# Develop_board.net
KiCad netlist of a schematic drawn in Altium Designer
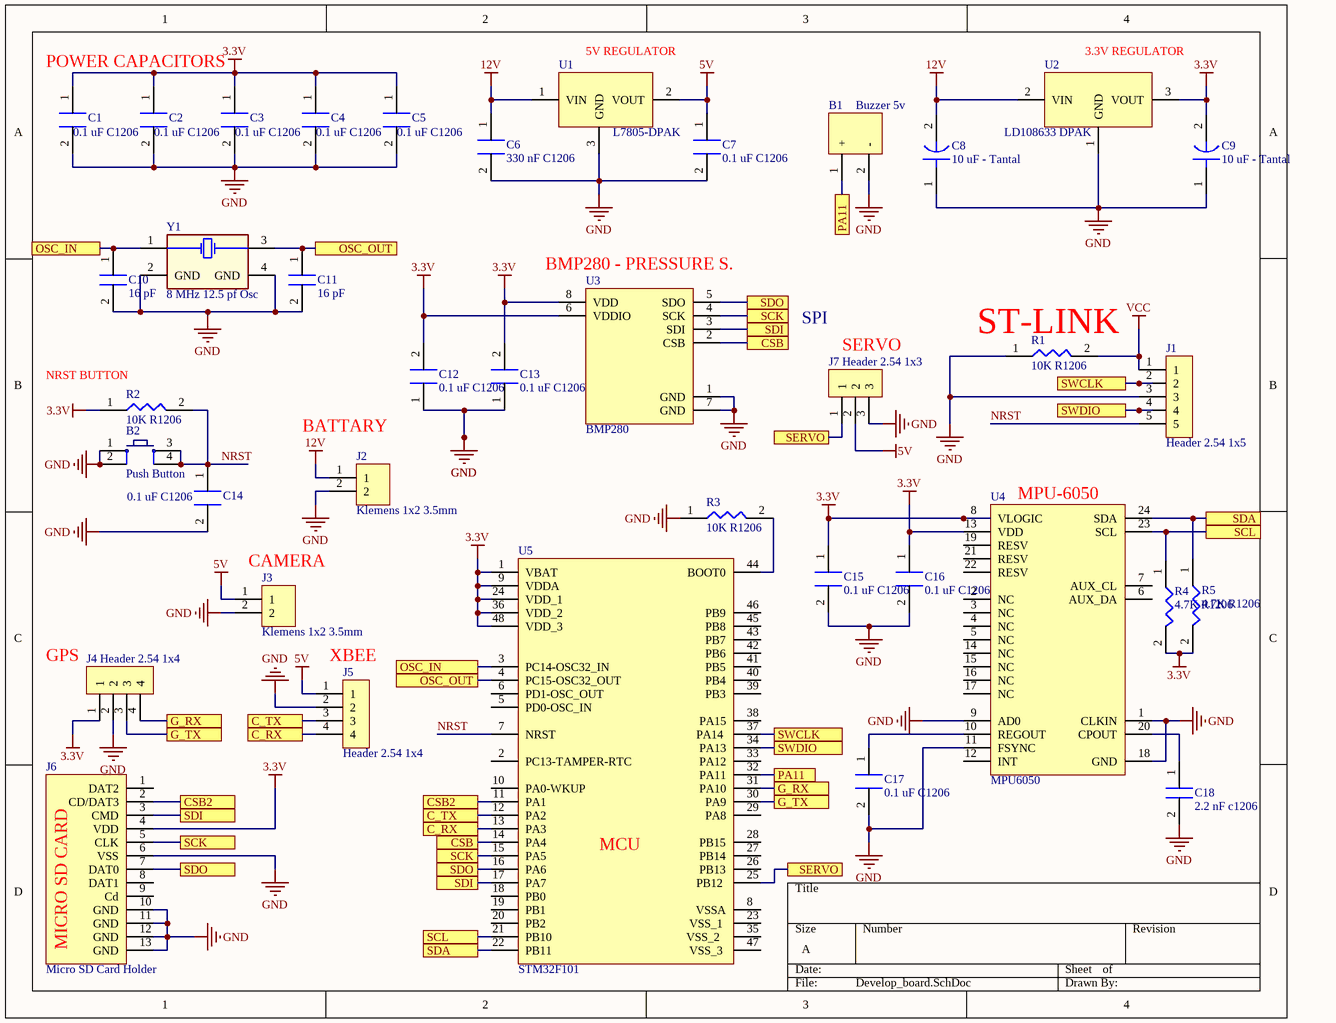
[diagram p0: Develop_board.SchDoc]

(export (version "E")
  (design (tool "Eeschema 10.0.6"))
  (components
    (comp (ref "B1")
      (value "Buzzer 5v")
      (footprint "Buzzer 5v")
      (libsource (lib "Schlib1") (part "Buzzer 5v"))
    )
    (comp (ref "B2")
      (value "Push Button")
      (footprint "PUSB BUTTON-SMD")
      (description "Smd Push Button")
      (libsource (lib "Schlib1") (part "Push Button"))
    )
    (comp (ref "C1")
      (value "0.1 uF C1206")
      (footprint "C1206")
      (libsource (lib "Schlib1") (part "0.1 uF C1206"))
    )
    (comp (ref "C2")
      (value "0.1 uF C1206")
      (footprint "C1206")
      (libsource (lib "Schlib1") (part "0.1 uF C1206"))
    )
    (comp (ref "C3")
      (value "0.1 uF C1206")
      (footprint "C1206")
      (libsource (lib "Schlib1") (part "0.1 uF C1206"))
    )
    (comp (ref "C4")
      (value "0.1 uF C1206")
      (footprint "C1206")
      (libsource (lib "Schlib1") (part "0.1 uF C1206"))
    )
    (comp (ref "C5")
      (value "0.1 uF C1206")
      (footprint "C1206")
      (libsource (lib "Schlib1") (part "0.1 uF C1206"))
    )
    (comp (ref "C6")
      (value "330 nF C1206")
      (footprint "C1206")
      (libsource (lib "Schlib1") (part "330 nF C1206"))
    )
    (comp (ref "C7")
      (value "0.1 uF C1206")
      (footprint "C1206")
      (libsource (lib "Schlib1") (part "0.1 uF C1206"))
    )
    (comp (ref "C8")
      (value "10 uF - Tantal")
      (footprint "C1206- TANTAL")
      (libsource (lib "Schlib1") (part "10 uF - Tantal"))
    )
    (comp (ref "C9")
      (value "10 uF - Tantal")
      (footprint "C1206- TANTAL")
      (libsource (lib "Schlib1") (part "10 uF - Tantal"))
    )
    (comp (ref "C10") (value "16 pF") (footprint "C1206") (libsource (lib "Schlib1") (part "16 pF")))
    (comp (ref "C11") (value "16 pF") (footprint "C1206") (libsource (lib "Schlib1") (part "16 pF")))
    (comp (ref "C12")
      (value "0.1 uF C1206")
      (footprint "C1206")
      (libsource (lib "Schlib1") (part "0.1 uF C1206"))
    )
    (comp (ref "C13")
      (value "0.1 uF C1206")
      (footprint "C1206")
      (libsource (lib "Schlib1") (part "0.1 uF C1206"))
    )
    (comp (ref "C14")
      (value "0.1 uF C1206")
      (footprint "C1206")
      (libsource (lib "Schlib1") (part "0.1 uF C1206"))
    )
    (comp (ref "C15")
      (value "0.1 uF C1206")
      (footprint "C1206")
      (libsource (lib "Schlib1") (part "0.1 uF C1206"))
    )
    (comp (ref "C16")
      (value "0.1 uF C1206")
      (footprint "C1206")
      (libsource (lib "Schlib1") (part "0.1 uF C1206"))
    )
    (comp (ref "C17")
      (value "0.1 uF C1206")
      (footprint "C1206")
      (libsource (lib "Schlib1") (part "0.1 uF C1206"))
    )
    (comp (ref "C18")
      (value "2.2 nF c1206")
      (footprint "C1206")
      (libsource (lib "Schlib1") (part "2.2 nF c1206"))
    )
    (comp (ref "J1")
      (value "Header 2.54 1x5")
      (footprint "Header 2.54 1x5")
      (libsource (lib "Schlib1") (part "Header 2.54 1x5"))
    )
    (comp (ref "J2")
      (value "Klemens 1x2 3.5mm")
      (footprint "Klemens 1x2 - 3.5mm")
      (libsource (lib "Schlib1") (part "Klemens 1x2 3.5mm"))
    )
    (comp (ref "J3")
      (value "Klemens 1x2 3.5mm")
      (footprint "Klemens 1x2 - 3.5mm")
      (libsource (lib "Schlib1") (part "Klemens 1x2 3.5mm"))
    )
    (comp (ref "J4")
      (value "Header 2.54 1x4")
      (footprint "Header 2.54 1x4")
      (libsource (lib "Schlib1") (part "Header 2.54 1x4"))
    )
    (comp (ref "J5")
      (value "Header 2.54 1x4")
      (footprint "Header 2.54 1x4")
      (libsource (lib "") (part "Header 2.54 1x4_1"))
    )
    (comp (ref "J6")
      (value "Micro SD Card Holder")
      (footprint "Micro SD Card Holder")
      (libsource (lib "Schlib1") (part "Micro SD Card Holder"))
    )
    (comp (ref "J7")
      (value "Header 2.54 1x3")
      (footprint "Header 2.54 1x3")
      (libsource (lib "Schlib1") (part "Header 2.54 1x3"))
    )
    (comp (ref "R1")
      (value "10K R1206")
      (footprint "R1206 Resistor")
      (description "4.7K R1206")
      (libsource (lib "Schlib1") (part "4.7K R1206"))
    )
    (comp (ref "R2")
      (value "10K R1206")
      (footprint "R1206 Resistor")
      (libsource (lib "Schlib1") (part "10K R1206"))
    )
    (comp (ref "R3")
      (value "10K R1206")
      (footprint "R1206 Resistor")
      (libsource (lib "Schlib1") (part "10K R1206"))
    )
    (comp (ref "R4")
      (value "4.7K R1206")
      (footprint "R1206 Resistor")
      (libsource (lib "Schlib1") (part "4.7K R1206"))
    )
    (comp (ref "R5")
      (value "4.7K R1206")
      (footprint "R1206 Resistor")
      (libsource (lib "Schlib1") (part "4.7K R1206"))
    )
    (comp (ref "U1")
      (value "L7805-DPAK")
      (footprint "DPAK228P972X230-3N")
      (description "L7805 5V REGULATOR. SMD PAKET")
      (libsource (lib "Schlib1") (part "L7805-DPAK"))
    )
    (comp (ref "U2")
      (value "LD108633 DPAK")
      (footprint "DPAK228P972X230-3N")
      (description "LD1086 3.3V REGULATOR")
      (libsource (lib "Schlib1") (part "LD108633 DPAK"))
    )
    (comp (ref "U3")
      (value "BMP280")
      (footprint "BMP280")
      (description "BMP280 SENSOR")
      (libsource (lib "Schlib1") (part "BMP280"))
    )
    (comp (ref "U4")
      (value "MPU6050")
      (footprint "QFN50P400X400X90_HS-25N")
      (description "MPU6050 GYRO SENSOR")
      (libsource (lib "Schlib1") (part "MPU6050"))
    )
    (comp (ref "U5")
      (value "STM32F101")
      (footprint "LQFP48-STM")
      (description "STM32F101 48 PİNLİ MİKROİŞLEMCİ")
      (libsource (lib "Schlib1") (part "STM32F101"))
    )
    (comp (ref "Y1")
      (value "8 MHz 12.5 pf Osc")
      (footprint "8 MHZ Osc.")
      (libsource (lib "Schlib1") (part "8 MHz 12.5 pf Osc"))
    )
  )
  (nets
    (net (code "1") (name "/CSB") (class "Default")
      (node (ref "U3") (pin "2") (pinfunction "CSB_2") (pintype "passive"))
      (node (ref "U5") (pin "14") (pinfunction "PA4_14") (pintype "passive"))
    )
    (net (code "2") (name "/CSB2") (class "Default")
      (node (ref "J6") (pin "2") (pinfunction "CD/DAT3_2") (pintype "passive"))
      (node (ref "U5") (pin "11") (pinfunction "PA1_11") (pintype "passive"))
    )
    (net (code "3") (name "/C_RX") (class "Default")
      (node (ref "J5") (pin "4") (pinfunction "4_4") (pintype "passive"))
      (node (ref "U5") (pin "13") (pinfunction "PA3_13") (pintype "passive"))
    )
    (net (code "4") (name "/C_TX") (class "Default")
      (node (ref "J5") (pin "3") (pinfunction "3_3") (pintype "passive"))
      (node (ref "U5") (pin "12") (pinfunction "PA2_12") (pintype "passive"))
    )
    (net (code "5") (name "/G_RX") (class "Default")
      (node (ref "J4") (pin "4") (pinfunction "4_4") (pintype "passive"))
      (node (ref "U5") (pin "31") (pinfunction "PA10_31") (pintype "passive"))
    )
    (net (code "6") (name "/G_TX") (class "Default")
      (node (ref "J4") (pin "3") (pinfunction "3_3") (pintype "passive"))
      (node (ref "U5") (pin "30") (pinfunction "PA9_30") (pintype "passive"))
    )
    (net (code "7") (name "/NRST") (class "Default")
      (node (ref "B2") (pin "3") (pinfunction "3_3") (pintype "passive"))
      (node (ref "B2") (pin "4") (pinfunction "4_4") (pintype "passive"))
      (node (ref "C14") (pin "1") (pinfunction "1_1") (pintype "passive"))
      (node (ref "J1") (pin "5") (pinfunction "5_5") (pintype "passive"))
      (node (ref "R2") (pin "2") (pinfunction "2_2") (pintype "passive"))
      (node (ref "U5") (pin "7") (pinfunction "NRST_7") (pintype "passive"))
    )
    (net (code "8") (name "/OSC_IN") (class "Default")
      (node (ref "C10") (pin "1") (pinfunction "1_1") (pintype "passive"))
      (node (ref "U5") (pin "3") (pinfunction "PC14-OSC32_IN_3") (pintype "passive"))
      (node (ref "Y1") (pin "1") (pintype "power_in"))
    )
    (net (code "9") (name "/OSC_OUT") (class "Default")
      (node (ref "C11") (pin "1") (pinfunction "1_1") (pintype "passive"))
      (node (ref "U5") (pin "4") (pinfunction "PC15-OSC32_OUT_4") (pintype "passive"))
      (node (ref "Y1") (pin "3") (pintype "passive"))
    )
    (net (code "10") (name "/PA11") (class "Default")
      (node (ref "B1") (pin "1") (pinfunction "+_1") (pintype "passive"))
      (node (ref "U5") (pin "32") (pinfunction "PA11_32") (pintype "passive"))
    )
    (net (code "11") (name "/SCK") (class "Default")
      (node (ref "J6") (pin "5") (pinfunction "CLK_5") (pintype "passive"))
      (node (ref "U3") (pin "4") (pinfunction "SCK_4") (pintype "passive"))
      (node (ref "U5") (pin "15") (pinfunction "PA5_15") (pintype "passive"))
    )
    (net (code "12") (name "/SCL") (class "Default")
      (node (ref "R4") (pin "1") (pinfunction "1_1") (pintype "passive"))
      (node (ref "U4") (pin "23") (pinfunction "SCL_23") (pintype "passive"))
      (node (ref "U5") (pin "21") (pinfunction "PB10_21") (pintype "passive"))
    )
    (net (code "13") (name "/SDA") (class "Default")
      (node (ref "R5") (pin "1") (pinfunction "1_1") (pintype "passive"))
      (node (ref "U4") (pin "24") (pinfunction "SDA_24") (pintype "passive"))
      (node (ref "U5") (pin "22") (pinfunction "PB11_22") (pintype "passive"))
    )
    (net (code "14") (name "/SDI") (class "Default")
      (node (ref "J6") (pin "3") (pinfunction "CMD_3") (pintype "passive"))
      (node (ref "U3") (pin "3") (pinfunction "SDI_3") (pintype "passive"))
      (node (ref "U5") (pin "17") (pinfunction "PA7_17") (pintype "passive"))
    )
    (net (code "15") (name "/SDO") (class "Default")
      (node (ref "J6") (pin "7") (pinfunction "DAT0_7") (pintype "passive"))
      (node (ref "U3") (pin "5") (pinfunction "SDO_5") (pintype "passive"))
      (node (ref "U5") (pin "16") (pinfunction "PA6_16") (pintype "passive"))
    )
    (net (code "16") (name "/SERVO") (class "Default")
      (node (ref "J7") (pin "1") (pinfunction "1_1") (pintype "passive"))
      (node (ref "U5") (pin "25") (pinfunction "PB12_25") (pintype "passive"))
    )
    (net (code "17") (name "/SWCLK") (class "Default")
      (node (ref "J1") (pin "2") (pinfunction "2_2") (pintype "passive"))
      (node (ref "U5") (pin "37") (pinfunction "PA14_37") (pintype "passive"))
    )
    (net (code "18") (name "/SWDIO") (class "Default")
      (node (ref "J1") (pin "4") (pinfunction "4_4") (pintype "passive"))
      (node (ref "U5") (pin "34") (pinfunction "PA13_34") (pintype "passive"))
    )
    (net (code "19") (name "3.3V") (class "Default")
      (node (ref "C1") (pin "1") (pinfunction "1_1") (pintype "passive"))
      (node (ref "C12") (pin "2") (pinfunction "2_2") (pintype "passive"))
      (node (ref "C13") (pin "2") (pinfunction "2_2") (pintype "passive"))
      (node (ref "C15") (pin "1") (pinfunction "1_1") (pintype "passive"))
      (node (ref "C16") (pin "1") (pinfunction "1_1") (pintype "passive"))
      (node (ref "C2") (pin "1") (pinfunction "1_1") (pintype "passive"))
      (node (ref "C3") (pin "1") (pinfunction "1_1") (pintype "passive"))
      (node (ref "C4") (pin "1") (pinfunction "1_1") (pintype "passive"))
      (node (ref "C5") (pin "1") (pinfunction "1_1") (pintype "passive"))
      (node (ref "C9") (pin "2") (pinfunction "2_2") (pintype "passive"))
      (node (ref "J4") (pin "1") (pinfunction "1_1") (pintype "passive"))
      (node (ref "J6") (pin "4") (pinfunction "VDD_4") (pintype "passive"))
      (node (ref "R2") (pin "1") (pinfunction "1_1") (pintype "passive"))
      (node (ref "R4") (pin "2") (pinfunction "2_2") (pintype "passive"))
      (node (ref "R5") (pin "2") (pinfunction "2_2") (pintype "passive"))
      (node (ref "U2") (pin "3") (pinfunction "VOUT_3") (pintype "passive"))
      (node (ref "U3") (pin "6") (pinfunction "VDDIO_6") (pintype "passive"))
      (node (ref "U3") (pin "8") (pinfunction "VDD_8") (pintype "passive"))
      (node (ref "U4") (pin "13") (pinfunction "VDD_13") (pintype "passive"))
      (node (ref "U4") (pin "8") (pinfunction "VLOGIC_8") (pintype "passive"))
      (node (ref "U5") (pin "1") (pinfunction "VBAT_1") (pintype "passive"))
      (node (ref "U5") (pin "24") (pinfunction "VDD_1_24") (pintype "passive"))
      (node (ref "U5") (pin "36") (pinfunction "VDD_2_36") (pintype "passive"))
      (node (ref "U5") (pin "48") (pinfunction "VDD_3_48") (pintype "passive"))
      (node (ref "U5") (pin "9") (pinfunction "VDDA_9") (pintype "passive"))
    )
    (net (code "20") (name "5V") (class "Default")
      (node (ref "C7") (pin "1") (pinfunction "1_1") (pintype "passive"))
      (node (ref "J3") (pin "1") (pinfunction "1_1") (pintype "passive"))
      (node (ref "J5") (pin "1") (pinfunction "1_1") (pintype "passive"))
      (node (ref "J7") (pin "2") (pinfunction "2_2") (pintype "passive"))
      (node (ref "U1") (pin "2") (pinfunction "VOUT_2") (pintype "passive"))
    )
    (net (code "21") (name "12V") (class "Default")
      (node (ref "C6") (pin "1") (pinfunction "1_1") (pintype "passive"))
      (node (ref "C8") (pin "2") (pinfunction "2_2") (pintype "passive"))
      (node (ref "J2") (pin "1") (pinfunction "1_1") (pintype "passive"))
      (node (ref "U1") (pin "1") (pinfunction "VIN_1") (pintype "passive"))
      (node (ref "U2") (pin "2") (pinfunction "VIN_2") (pintype "passive"))
    )
    (net (code "22") (name "GND") (class "Default")
      (node (ref "B1") (pin "2") (pinfunction "-_2") (pintype "passive"))
      (node (ref "B2") (pin "1") (pinfunction "1_1") (pintype "passive"))
      (node (ref "B2") (pin "2") (pinfunction "2_2") (pintype "passive"))
      (node (ref "C1") (pin "2") (pinfunction "2_2") (pintype "passive"))
      (node (ref "C10") (pin "2") (pinfunction "2_2") (pintype "passive"))
      (node (ref "C11") (pin "2") (pinfunction "2_2") (pintype "passive"))
      (node (ref "C12") (pin "1") (pinfunction "1_1") (pintype "passive"))
      (node (ref "C13") (pin "1") (pinfunction "1_1") (pintype "passive"))
      (node (ref "C14") (pin "2") (pinfunction "2_2") (pintype "passive"))
      (node (ref "C15") (pin "2") (pinfunction "2_2") (pintype "passive"))
      (node (ref "C16") (pin "2") (pinfunction "2_2") (pintype "passive"))
      (node (ref "C17") (pin "2") (pinfunction "2_2") (pintype "passive"))
      (node (ref "C18") (pin "2") (pinfunction "2_2") (pintype "passive"))
      (node (ref "C2") (pin "2") (pinfunction "2_2") (pintype "passive"))
      (node (ref "C3") (pin "2") (pinfunction "2_2") (pintype "passive"))
      (node (ref "C4") (pin "2") (pinfunction "2_2") (pintype "passive"))
      (node (ref "C5") (pin "2") (pinfunction "2_2") (pintype "passive"))
      (node (ref "C6") (pin "2") (pinfunction "2_2") (pintype "passive"))
      (node (ref "C7") (pin "2") (pinfunction "2_2") (pintype "passive"))
      (node (ref "C8") (pin "1") (pinfunction "1_1") (pintype "passive"))
      (node (ref "C9") (pin "1") (pinfunction "1_1") (pintype "passive"))
      (node (ref "J1") (pin "3") (pinfunction "3_3") (pintype "passive"))
      (node (ref "J2") (pin "2") (pinfunction "2_2") (pintype "passive"))
      (node (ref "J3") (pin "2") (pinfunction "2_2") (pintype "passive"))
      (node (ref "J4") (pin "2") (pinfunction "2_2") (pintype "passive"))
      (node (ref "J5") (pin "2") (pinfunction "2_2") (pintype "passive"))
      (node (ref "J6") (pin "10") (pinfunction "GND_10") (pintype "passive"))
      (node (ref "J6") (pin "11") (pinfunction "GND_11") (pintype "passive"))
      (node (ref "J6") (pin "12") (pinfunction "GND_12") (pintype "passive"))
      (node (ref "J6") (pin "13") (pinfunction "GND_13") (pintype "passive"))
      (node (ref "J6") (pin "6") (pinfunction "VSS_6") (pintype "passive"))
      (node (ref "J7") (pin "3") (pinfunction "3_3") (pintype "passive"))
      (node (ref "R1") (pin "1") (pinfunction "1_1") (pintype "passive"))
      (node (ref "R3") (pin "1") (pinfunction "1_1") (pintype "passive"))
      (node (ref "U1") (pin "3") (pinfunction "GND_3") (pintype "passive"))
      (node (ref "U2") (pin "1") (pinfunction "GND_1") (pintype "passive"))
      (node (ref "U3") (pin "1") (pinfunction "GND_1") (pintype "passive"))
      (node (ref "U3") (pin "7") (pinfunction "GND_7") (pintype "passive"))
      (node (ref "U4") (pin "1") (pinfunction "CLKIN_1") (pintype "passive"))
      (node (ref "U4") (pin "11") (pinfunction "FSYNC_11") (pintype "passive"))
      (node (ref "U4") (pin "18") (pinfunction "GND_18") (pintype "passive"))
      (node (ref "U4") (pin "9") (pinfunction "AD0_9") (pintype "passive"))
      (node (ref "Y1") (pin "2") (pinfunction "GND_2") (pintype "power_in"))
      (node (ref "Y1") (pin "4") (pinfunction "GND_4") (pintype "passive"))
    )
    (net (code "23") (name "Net-(U4-CPOUT)") (class "Default")
      (node (ref "C18") (pin "1") (pinfunction "1_1") (pintype "passive"))
      (node (ref "U4") (pin "20") (pinfunction "CPOUT_20") (pintype "passive"))
    )
    (net (code "24") (name "Net-(U4-REGOUT)") (class "Default")
      (node (ref "C17") (pin "1") (pinfunction "1_1") (pintype "passive"))
      (node (ref "U4") (pin "10") (pinfunction "REGOUT_10") (pintype "passive"))
    )
    (net (code "25") (name "Net-(U5-BOOT0)") (class "Default")
      (node (ref "R3") (pin "2") (pinfunction "2_2") (pintype "passive"))
      (node (ref "U5") (pin "44") (pinfunction "BOOT0_44") (pintype "passive"))
    )
    (net (code "26") (name "VCC") (class "Default")
      (node (ref "J1") (pin "1") (pinfunction "1_1") (pintype "passive"))
      (node (ref "R1") (pin "2") (pinfunction "2_2") (pintype "passive"))
    )
    (net (code "27") (name "unconnected-(J6-Cd-Pad9)") (class "Default")
      (node (ref "J6") (pin "9") (pinfunction "Cd_9") (pintype "passive"))
    )
    (net (code "28") (name "unconnected-(J6-DAT1-Pad8)") (class "Default")
      (node (ref "J6") (pin "8") (pinfunction "DAT1_8") (pintype "passive"))
    )
    (net (code "29") (name "unconnected-(J6-DAT2-Pad1)") (class "Default")
      (node (ref "J6") (pin "1") (pinfunction "DAT2_1") (pintype "passive"))
    )
    (net (code "30") (name "unconnected-(U4-AUX_CL-Pad7)") (class "Default")
      (node (ref "U4") (pin "7") (pinfunction "AUX_CL_7") (pintype "passive"))
    )
    (net (code "31") (name "unconnected-(U4-AUX_DA-Pad6)") (class "Default")
      (node (ref "U4") (pin "6") (pinfunction "AUX_DA_6") (pintype "passive"))
    )
    (net (code "32") (name "unconnected-(U4-INT-Pad12)") (class "Default")
      (node (ref "U4") (pin "12") (pinfunction "INT_12") (pintype "passive"))
    )
    (net (code "33") (name "unconnected-(U4-NC-Pad2)") (class "Default")
      (node (ref "U4") (pin "2") (pinfunction "NC_2") (pintype "passive"))
    )
    (net (code "34") (name "unconnected-(U4-NC-Pad3)") (class "Default")
      (node (ref "U4") (pin "3") (pinfunction "NC_3") (pintype "passive"))
    )
    (net (code "35") (name "unconnected-(U4-NC-Pad4)") (class "Default")
      (node (ref "U4") (pin "4") (pinfunction "NC_4") (pintype "passive"))
    )
    (net (code "36") (name "unconnected-(U4-NC-Pad5)") (class "Default")
      (node (ref "U4") (pin "5") (pinfunction "NC_5") (pintype "passive"))
    )
    (net (code "37") (name "unconnected-(U4-NC-Pad14)") (class "Default")
      (node (ref "U4") (pin "14") (pinfunction "NC_14") (pintype "passive"))
    )
    (net (code "38") (name "unconnected-(U4-NC-Pad15)") (class "Default")
      (node (ref "U4") (pin "15") (pinfunction "NC_15") (pintype "passive"))
    )
    (net (code "39") (name "unconnected-(U4-NC-Pad16)") (class "Default")
      (node (ref "U4") (pin "16") (pinfunction "NC_16") (pintype "passive"))
    )
    (net (code "40") (name "unconnected-(U4-NC-Pad17)") (class "Default")
      (node (ref "U4") (pin "17") (pinfunction "NC_17") (pintype "passive"))
    )
    (net (code "41") (name "unconnected-(U4-RESV-Pad19)") (class "Default")
      (node (ref "U4") (pin "19") (pinfunction "RESV_19") (pintype "passive"))
    )
    (net (code "42") (name "unconnected-(U4-RESV-Pad21)") (class "Default")
      (node (ref "U4") (pin "21") (pinfunction "RESV_21") (pintype "passive"))
    )
    (net (code "43") (name "unconnected-(U4-RESV-Pad22)") (class "Default")
      (node (ref "U4") (pin "22") (pinfunction "RESV_22") (pintype "passive"))
    )
    (net (code "44") (name "unconnected-(U5-PA0-WKUP-Pad10)") (class "Default")
      (node (ref "U5") (pin "10") (pinfunction "PA0-WKUP_10") (pintype "passive"))
    )
    (net (code "45") (name "unconnected-(U5-PA8-Pad29)") (class "Default")
      (node (ref "U5") (pin "29") (pinfunction "PA8_29") (pintype "passive"))
    )
    (net (code "46") (name "unconnected-(U5-PA12-Pad33)") (class "Default")
      (node (ref "U5") (pin "33") (pinfunction "PA12_33") (pintype "passive"))
    )
    (net (code "47") (name "unconnected-(U5-PA15-Pad38)") (class "Default")
      (node (ref "U5") (pin "38") (pinfunction "PA15_38") (pintype "passive"))
    )
    (net (code "48") (name "unconnected-(U5-PB0-Pad18)") (class "Default")
      (node (ref "U5") (pin "18") (pinfunction "PB0_18") (pintype "passive"))
    )
    (net (code "49") (name "unconnected-(U5-PB1-Pad19)") (class "Default")
      (node (ref "U5") (pin "19") (pinfunction "PB1_19") (pintype "passive"))
    )
    (net (code "50") (name "unconnected-(U5-PB2-Pad20)") (class "Default")
      (node (ref "U5") (pin "20") (pinfunction "PB2_20") (pintype "passive"))
    )
    (net (code "51") (name "unconnected-(U5-PB3-Pad39)") (class "Default")
      (node (ref "U5") (pin "39") (pinfunction "PB3_39") (pintype "passive"))
    )
    (net (code "52") (name "unconnected-(U5-PB4-Pad40)") (class "Default")
      (node (ref "U5") (pin "40") (pinfunction "PB4_40") (pintype "passive"))
    )
    (net (code "53") (name "unconnected-(U5-PB5-Pad41)") (class "Default")
      (node (ref "U5") (pin "41") (pinfunction "PB5_41") (pintype "passive"))
    )
    (net (code "54") (name "unconnected-(U5-PB6-Pad42)") (class "Default")
      (node (ref "U5") (pin "42") (pinfunction "PB6_42") (pintype "passive"))
    )
    (net (code "55") (name "unconnected-(U5-PB7-Pad43)") (class "Default")
      (node (ref "U5") (pin "43") (pinfunction "PB7_43") (pintype "passive"))
    )
    (net (code "56") (name "unconnected-(U5-PB8-Pad45)") (class "Default")
      (node (ref "U5") (pin "45") (pinfunction "PB8_45") (pintype "passive"))
    )
    (net (code "57") (name "unconnected-(U5-PB9-Pad46)") (class "Default")
      (node (ref "U5") (pin "46") (pinfunction "PB9_46") (pintype "passive"))
    )
    (net (code "58") (name "unconnected-(U5-PB13-Pad26)") (class "Default")
      (node (ref "U5") (pin "26") (pinfunction "PB13_26") (pintype "passive"))
    )
    (net (code "59") (name "unconnected-(U5-PB14-Pad27)") (class "Default")
      (node (ref "U5") (pin "27") (pinfunction "PB14_27") (pintype "passive"))
    )
    (net (code "60") (name "unconnected-(U5-PB15-Pad28)") (class "Default")
      (node (ref "U5") (pin "28") (pinfunction "PB15_28") (pintype "passive"))
    )
    (net (code "61") (name "unconnected-(U5-PC13-TAMPER-RTC-Pad2)") (class "Default")
      (node (ref "U5") (pin "2") (pinfunction "PC13-TAMPER-RTC_2") (pintype "passive"))
    )
    (net (code "62") (name "unconnected-(U5-PD0-OSC_IN-Pad5)") (class "Default")
      (node (ref "U5") (pin "5") (pinfunction "PD0-OSC_IN_5") (pintype "passive"))
    )
    (net (code "63") (name "unconnected-(U5-PD1-OSC_OUT-Pad6)") (class "Default")
      (node (ref "U5") (pin "6") (pinfunction "PD1-OSC_OUT_6") (pintype "passive"))
    )
    (net (code "64") (name "unconnected-(U5-VSSA-Pad8)") (class "Default")
      (node (ref "U5") (pin "8") (pinfunction "VSSA_8") (pintype "passive"))
    )
    (net (code "65") (name "unconnected-(U5-VSS_1-Pad23)") (class "Default")
      (node (ref "U5") (pin "23") (pinfunction "VSS_1_23") (pintype "passive"))
    )
    (net (code "66") (name "unconnected-(U5-VSS_2-Pad35)") (class "Default")
      (node (ref "U5") (pin "35") (pinfunction "VSS_2_35") (pintype "passive"))
    )
    (net (code "67") (name "unconnected-(U5-VSS_3-Pad47)") (class "Default")
      (node (ref "U5") (pin "47") (pinfunction "VSS_3_47") (pintype "passive"))
    )
  )
)
